# rad_detector_v500_CONN.net
KiCad netlist of a schematic drawn in Altium Designer
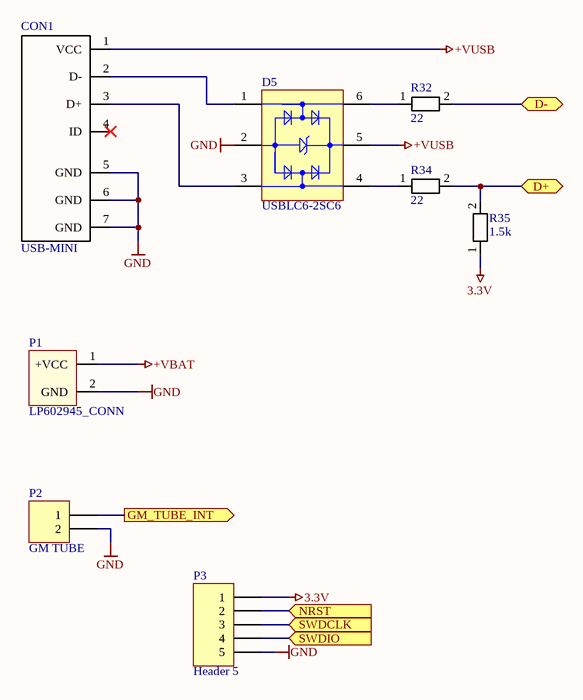
[diagram p0: rad_detector_v500_CONN.SchDoc]

(export (version "E")
  (design (tool "Eeschema 10.0.6"))
  (components
    (comp (ref "CON1")
      (value "USB-MINI")
      (footprint "USB-MINI")
      (libsource (lib "Schlib1") (part "USB-MINI"))
    )
    (comp (ref "D5")
      (value "USBLC6-2SC6")
      (footprint "STM-SOT23-6L_V")
      (description "Very low capacitance ESD protection, 3.5 pF, -40 to 125 degC, 6-Pin SOT23, RoHS, Tape and Reel")
      (fields (field (name "MANUFACTURER") "STMicroelectronics"))
      (libsource (lib "ic_modules") (part "USBLC6-2SC6"))
    )
    (comp (ref "P1")
      (value "LP602945_CONN")
      (footprint "LP602945_CONN")
      (libsource (lib "Schlib1") (part "LP602945_CONN"))
    )
    (comp (ref "P2")
      (value "GM TUBE")
      (footprint "HDR1X2")
      (description "Header, 2-Pin")
      (fields (field (name "PUBLISHER") "Altium Limited"))
      (libsource (lib "Miscellaneous Connectors") (part "Header 2"))
    )
    (comp (ref "P3")
      (value "Header 5")
      (footprint "HDR1X5")
      (description "Header, 5-Pin")
      (fields (field (name "PUBLISHER") "Altium Limited"))
      (libsource (lib "Miscellaneous Connectors") (part "Header 5"))
    )
    (comp (ref "R32") (value "22") (footprint "0805") (libsource (lib "Schlib1") (part "RESISTOR")))
    (comp (ref "R34") (value "22") (footprint "0805") (libsource (lib "Schlib1") (part "RESISTOR")))
    (comp (ref "R35") (value "1.5k") (footprint "0805") (libsource (lib "Schlib1") (part "RESISTOR")))
  )
  (nets
    (net (code "1") (name "+VBAT") (class "Default")
      (node (ref "P1") (pin "1") (pinfunction "+VCC_1") (pintype "passive"))
    )
    (net (code "2") (name "+VUSB") (class "Default")
      (node (ref "CON1") (pin "1") (pinfunction "VCC_1") (pintype "power_in"))
      (node (ref "D5") (pin "5") (pinfunction "VBUS_5") (pintype "passive"))
    )
    (net (code "3") (name "/D+") (class "Default")
      (node (ref "R34") (pin "2") (pinfunction "1_2") (pintype "passive"))
      (node (ref "R35") (pin "2") (pinfunction "1_2") (pintype "passive"))
    )
    (net (code "4") (name "/D-") (class "Default")
      (node (ref "R32") (pin "2") (pinfunction "1_2") (pintype "passive"))
    )
    (net (code "5") (name "/GM_TUBE_INT") (class "Default")
      (node (ref "P2") (pin "1") (pinfunction "1_1") (pintype "passive"))
    )
    (net (code "6") (name "/NRST") (class "Default")
      (node (ref "P3") (pin "2") (pinfunction "2_2") (pintype "passive"))
    )
    (net (code "7") (name "/SWDCLK") (class "Default")
      (node (ref "P3") (pin "3") (pinfunction "3_3") (pintype "passive"))
    )
    (net (code "8") (name "/SWDIO") (class "Default")
      (node (ref "P3") (pin "4") (pinfunction "4_4") (pintype "passive"))
    )
    (net (code "9") (name "3.3V") (class "Default")
      (node (ref "P3") (pin "1") (pinfunction "1_1") (pintype "passive"))
      (node (ref "R35") (pin "1") (pinfunction "0_1") (pintype "passive"))
    )
    (net (code "10") (name "GND") (class "Default")
      (node (ref "CON1") (pin "5") (pinfunction "GND_5") (pintype "passive"))
      (node (ref "CON1") (pin "6") (pinfunction "GND_6") (pintype "passive"))
      (node (ref "CON1") (pin "7") (pinfunction "GND_7") (pintype "passive"))
      (node (ref "D5") (pin "2") (pinfunction "GND_2") (pintype "passive"))
      (node (ref "P1") (pin "2") (pinfunction "GND_2") (pintype "passive"))
      (node (ref "P2") (pin "2") (pinfunction "2_2") (pintype "passive"))
      (node (ref "P3") (pin "5") (pinfunction "5_5") (pintype "passive"))
    )
    (net (code "11") (name "Net-(CON1-D+)") (class "Default")
      (node (ref "CON1") (pin "3") (pinfunction "D+_3") (pintype "passive"))
      (node (ref "D5") (pin "3") (pinfunction "I/O_2_3") (pintype "passive"))
    )
    (net (code "12") (name "Net-(CON1-D-)") (class "Default")
      (node (ref "CON1") (pin "2") (pinfunction "D-_2") (pintype "passive"))
      (node (ref "D5") (pin "1") (pinfunction "I/O_1_1") (pintype "passive"))
    )
    (net (code "13") (name "Net-(D5-I{slash}O_3)") (class "Default")
      (node (ref "D5") (pin "4") (pinfunction "I/O_3_4") (pintype "passive"))
      (node (ref "R34") (pin "1") (pinfunction "0_1") (pintype "passive"))
    )
    (net (code "14") (name "Net-(D5-I{slash}O_4)") (class "Default")
      (node (ref "D5") (pin "6") (pinfunction "I/O_4_6") (pintype "passive"))
      (node (ref "R32") (pin "1") (pinfunction "0_1") (pintype "passive"))
    )
    (net (code "15") (name "unconnected-(CON1-ID-Pad4)") (class "Default")
      (node (ref "CON1") (pin "4") (pinfunction "ID_4") (pintype "passive+no_connect"))
    )
  )
)
